# SensorControl_Board_v3_1.net
KiCad netlist of a schematic drawn in Altium Designer
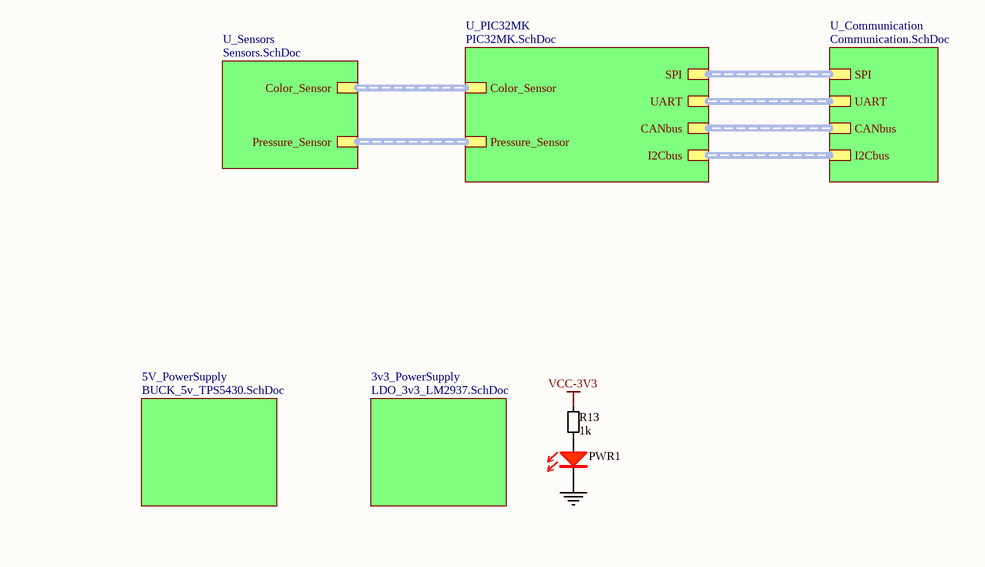
[diagram p0: SensorControl_Board_v3.1.SchDoc]

(export (version "E")
  (design (tool "Eeschema 10.0.6"))
  (components
    (comp (ref "PWR1")
      (value "LED RED")
      (footprint "LED_RED_0805")
      (description "LED RED 0805")
      (fields
        (field (name "MANUFACTURER") "BRIGHT LED ELECTRONICS")
        (field (name "MANUFACTURER PART NUMBER") "BL-HUB35A-AV-TRB")
      )
      (libsource (lib "Discrete_Semiconductor") (part "LED_RED_0805"))
    )
    (comp (ref "R13")
      (value "1k")
      (footprint "RESC2013X38N-0805-NOOVERLAY")
      (description "RES SMD 1 kOhm 1/8W 0805")
      (fields (field (name "POWER") "0.125W, 1/8W"))
      (libsource (lib "Resistors") (part "00001001"))
    )
  )
  (nets
    (net (code "7") (name "GND") (class "Default")
      (node (ref "PWR1") (pin "1") (pinfunction "C_1") (pintype "passive"))
    )
    (net (code "8") (name "Net-(PWR1-A)") (class "Default")
      (node (ref "PWR1") (pin "2") (pinfunction "A_2") (pintype "passive"))
      (node (ref "R13") (pin "1") (pinfunction "1_1") (pintype "passive"))
    )
    (net (code "9") (name "VCC-3V3") (class "Default")
      (node (ref "R13") (pin "2") (pinfunction "2_2") (pintype "passive"))
    )
  )
)
